# Hydro-Node.net
KiCad netlist of a schematic drawn in Altium Designer
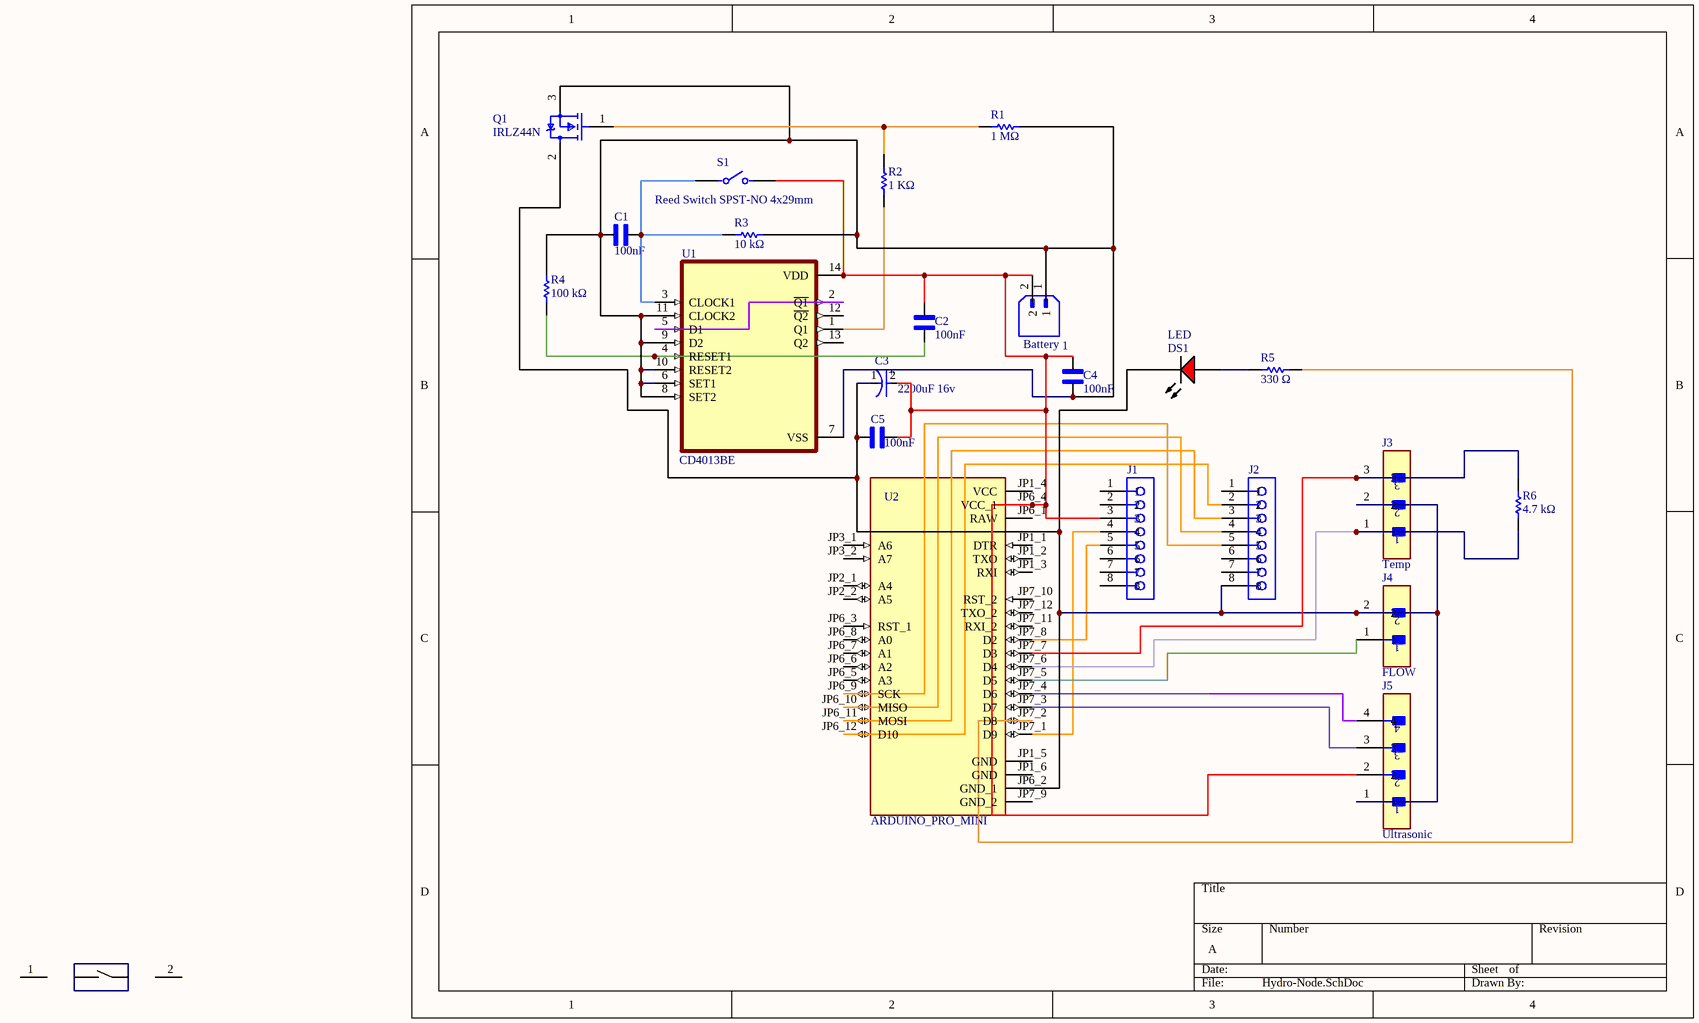
[diagram p0: Hydro-Node.SchDoc]

(export (version "E")
  (design (tool "Eeschema 10.0.6"))
  (components
    (comp (ref "1")
      (value "Battery")
      (footprint "JST_B2B-XH-A_(LF)(SN)")
      (description "Connector Header Through Hole 2 position 0.098 (2.50mm)")
      (fields (field (name "MF") "JST Sales") (field (name "MP") "B2B-XH-A (LF)(SN)"))
      (libsource (lib "B2B-XH-A__LF__SN_") (part "B2B-XH-A_(LF)(SN)"))
    )
    (comp (ref "C1")
      (value "100nF")
      (footprint "CAPRR508W50L508T317H508")
      (description "SR Series 5.08x5.08 mm 100 nF 50 V Â±20% Tol. Z5U Radial Lead/SkyCapÂ®")
      (fields (field (name "MF") "AVX") (field (name "MP") "SR215E104MARTR1"))
      (libsource (lib "") (part "SR215E104MARTR1._1"))
    )
    (comp (ref "C2")
      (value "100nF")
      (footprint "CAPRR508W50L508T317H508")
      (description "SR Series 5.08x5.08 mm 100 nF 50 V Â±20% Tol. Z5U Radial Lead/SkyCapÂ®")
      (fields (field (name "MF") "AVX") (field (name "MP") "SR215E104MARTR1"))
      (libsource (lib "SR215E104MARTR1.") (part "SR215E104MARTR1."))
    )
    (comp (ref "C3")
      (value "2200uF 16v")
      (footprint "FP-RAD-TH-D_10_0_5-L_16_1-MFG")
      (description "Aluminum Electrolytic Capacitors (Radial Lead Type) 2200uF ±20% 6.3V")
      (libsource (lib "Altium Content Vault") (part "a00bbbee19879c290e62620ae7e47b1"))
    )
    (comp (ref "C4")
      (value "100nF")
      (footprint "CAPRR508W50L508T317H508")
      (description "SR Series 5.08x5.08 mm 100 nF 50 V Â±20% Tol. Z5U Radial Lead/SkyCapÂ®")
      (fields (field (name "MF") "AVX") (field (name "MP") "SR215E104MARTR1"))
      (libsource (lib "SR215E104MARTR1.") (part "SR215E104MARTR1."))
    )
    (comp (ref "C5")
      (value "100nF")
      (footprint "CAPRR508W50L508T317H508")
      (description "SR Series 5.08x5.08 mm 100 nF 50 V Â±20% Tol. Z5U Radial Lead/SkyCapÂ®")
      (fields (field (name "MF") "AVX") (field (name "MP") "SR215E104MARTR1"))
      (libsource (lib "") (part "SR215E104MARTR1._1"))
    )
    (comp (ref "DS1")
      (value "LED")
      (footprint "INDPR60-254-520X380X650")
      (description "Radial LED, 12.6 mcd, 20 mA, 2 V, -55 to 100 degC, 2-Pin THD, RoHS, Bulk")
      (fields (field (name "TOLERANCE") "20%"))
      (libsource (lib "Altium Content Vault") (part "LED-RED-AK-2"))
    )
    (comp (ref "J1")
      (value "61300811821")
      (footprint "61300811821")
      (description "Btb Conn, Rcpt, 8Pos, 1Row, 2.54Mm Rohs Compliant: Yes")
      (libsource (lib "Altium Content Vault") (part "Header_Female_1R_08P"))
    )
    (comp (ref "J2")
      (value "61300811821")
      (footprint "61300811821")
      (description "Btb Conn, Rcpt, 8Pos, 1Row, 2.54Mm Rohs Compliant: Yes")
      (libsource (lib "Altium Content Vault") (part "Header_Female_1R_08P"))
    )
    (comp (ref "J3")
      (value "Temp")
      (footprint "FP-B3B-XH-A_LF_SN-MFG")
      (description "CONN HEADER VERT 3POS 2.5MM")
      (libsource (lib "Altium Content Vault") (part "0d3f023dd272f625e17a2be33dea85f"))
    )
    (comp (ref "J4")
      (value "FLOW")
      (footprint "FP-B2B-XH-AM_LF_SN-MFG")
      (description "CONN HEADER VERT 2POS 2.5MM")
      (libsource (lib "Altium Content Vault") (part "3bc925449376181038e59eaffc5286c"))
    )
    (comp (ref "J5")
      (value "Ultrasonic")
      (footprint "FP-B4B-XH-AM_LF_SN-MFG")
      (description "CONN HEADER VERT 4POS 2.5MM")
      (libsource (lib "Altium Content Vault") (part "299a8cea1bdcbc3624fe62c390fa72c"))
    )
    (comp (ref "Q1")
      (value "IRLZ44N")
      (footprint "FP-PG-TO220-3-MFG")
      (description "MOSFET N-CH 55V 47A TO220AB")
      (libsource (lib "Altium Content Vault") (part "b09f7f152735e370c1ea22a33fa83d6"))
    )
    (comp (ref "R1")
      (value "1 MΩ")
      (footprint "RESA60-630X240")
      (description "Axial Resistor, 1 MOhm, +/- 1%, 250 mW, -55 to 155 degC, 2-Pin THD, RoHS, Bulk")
      (fields (field (name "TOLERANCE") "1%"))
      (libsource (lib "Altium Content Vault") (part "RES-2"))
    )
    (comp (ref "R2")
      (value "1 KΩ")
      (footprint "RESA60-630X240")
      (description "Axial Resistor, 1 KOhm, +/- 1%, 250 mW, -55 to 155 degC, 2-Pin THD, RoHS, Bulk")
      (fields (field (name "TOLERANCE") "1%"))
      (libsource (lib "Altium Content Vault") (part "RES-2"))
    )
    (comp (ref "R3")
      (value "10 kΩ")
      (footprint "RESA60-630X240")
      (description "Axial Resistor, 10 KOhm, +/- 1%, 0.25 W, -55 to 155 degC, 2-Pin THD, RoHS, Bulk")
      (fields (field (name "TOLERANCE") "1%") (field (name "MANUFACTURER") "Yageo"))
      (libsource (lib "Altium Content Vault") (part "RES-2"))
    )
    (comp (ref "R4")
      (value "100 kΩ")
      (footprint "RESA60-630X240")
      (description "Axial Resistor, 100 KOhm, +/- 1%, 0.25 W, -55 to 155 degC, 2-Pin THD, RoHS, Bulk")
      (fields (field (name "TOLERANCE") "1%"))
      (libsource (lib "Altium Content Vault") (part "RES-2"))
    )
    (comp (ref "R5")
      (value "330 Ω")
      (footprint "RESA60-630X240")
      (description "Axial Resistor, 1 MOhm, +/- 1%, 250 mW, -55 to 155 degC, 2-Pin THD, RoHS, Bulk")
      (fields (field (name "TOLERANCE") "1%"))
      (libsource (lib "Altium Content Vault") (part "RES-2"))
    )
    (comp (ref "R6")
      (value "4.7 kΩ")
      (footprint "RESA60-630X240")
      (description "Axial Resistor, 4.75 KOhm, +/- 1%, 0.25 W, -55 to 155 degC, 2-Pin THD, RoHS, Bulk")
      (fields (field (name "TOLERANCE") "10%"))
      (libsource (lib "Altium Content Vault") (part "RES-2"))
    )
    (comp (ref "S1")
      (value "Reed Switch SPST-NO 4x29mm")
      (footprint "REEDSW-THT-D4L29-P35")
      (fields
        (field (name "MANUFACTURER PART NUMBER") "MDSM-4R-12-18")
        (field (name "OCTOPART") "https://octopart.com/mdsm-4r-12-18-littelfuse-55632078")
        (field (name "MANUFACTURER") "Littelfuse")
      )
      (libsource (lib "ReedSwitch") (part "REED-SWITCH-NO-D4L29"))
    )
    (comp (ref "U1")
      (value "CD4013BE")
      (footprint "DIP794W45P254L1969H508Q14")
      (description "CMOS Dual D-Type Flip Flop")
      (fields (field (name "MF") "Texas Instruments"))
      (libsource (lib "CD4013BE") (part "CD4013BE"))
    )
    (comp (ref "U2")
      (value "ARDUINO_PRO_MINI")
      (footprint "MODULE_ARDUINO_PRO_MINI")
      (fields (field (name "MF") "Arduino") (field (name "MP") "Arduino Pro Mini"))
      (libsource (lib "ARDUINO_PRO_MINI") (part "ARDUINO_PRO_MINI"))
    )
  )
  (nets
    (net (code "1") (name "Net-(C3-A)") (class "Default")
      (node (ref "1") (pin "2") (pinfunction "2_2") (pintype "passive"))
      (node (ref "C2") (pin "1") (pinfunction "1_1") (pintype "passive"))
      (node (ref "C3") (pin "2") (pinfunction "A_2") (pintype "passive"))
      (node (ref "C4") (pin "1") (pinfunction "1_1") (pintype "passive"))
      (node (ref "C5") (pin "2") (pinfunction "2_2") (pintype "passive"))
      (node (ref "J1") (pin "3") (pinfunction "3_3") (pintype "passive"))
      (node (ref "J5") (pin "2") (pinfunction "2_2") (pintype "passive"))
      (node (ref "S1") (pin "2") (pinfunction "2_2") (pintype "passive"))
      (node (ref "U1") (pin "14") (pinfunction "VDD_14") (pintype "power_in"))
      (node (ref "U2") (pin "JP6_4") (pinfunction "VCC_1_JP6_4") (pintype "power_in"))
    )
    (net (code "2") (name "Net-(C3-C)") (class "Default")
      (node (ref "C3") (pin "1") (pinfunction "C_1") (pintype "passive"))
      (node (ref "C5") (pin "1") (pinfunction "1_1") (pintype "passive"))
      (node (ref "DS1") (pin "2") (pinfunction "K_2") (pintype "passive"))
      (node (ref "J2") (pin "8") (pinfunction "8_8") (pintype "passive"))
      (node (ref "J3") (pin "2") (pinfunction "2_2") (pintype "passive"))
      (node (ref "J4") (pin "2") (pinfunction "2_2") (pintype "passive"))
      (node (ref "J5") (pin "1") (pinfunction "1_1") (pintype "passive"))
      (node (ref "Q1") (pin "2") (pinfunction "D_2") (pintype "passive"))
      (node (ref "U2") (pin "JP6_2") (pinfunction "GND_1_JP6_2") (pintype "power_in"))
    )
    (net (code "3") (name "Net-(DS1-A)") (class "Default")
      (node (ref "DS1") (pin "1") (pinfunction "A_1") (pintype "passive"))
      (node (ref "R5") (pin "1") (pinfunction "1_1") (pintype "passive"))
    )
    (net (code "4") (name "Net-(Q1-G)") (class "Default")
      (node (ref "Q1") (pin "1") (pinfunction "G_1") (pintype "passive"))
      (node (ref "R1") (pin "1") (pinfunction "1_1") (pintype "passive"))
      (node (ref "R2") (pin "2") (pinfunction "2_2") (pintype "passive"))
    )
    (net (code "5") (name "Net-(Q1-S)") (class "Default")
      (node (ref "1") (pin "1") (pinfunction "1_1") (pintype "passive"))
      (node (ref "C1") (pin "1") (pinfunction "1_1") (pintype "passive"))
      (node (ref "C4") (pin "2") (pinfunction "2_2") (pintype "passive"))
      (node (ref "Q1") (pin "3") (pinfunction "S_3") (pintype "passive"))
      (node (ref "R1") (pin "2") (pinfunction "2_2") (pintype "passive"))
      (node (ref "R3") (pin "2") (pinfunction "2_2") (pintype "passive"))
      (node (ref "R4") (pin "2") (pinfunction "2_2") (pintype "passive"))
      (node (ref "U1") (pin "10") (pinfunction "RESET2_10") (pintype "input"))
      (node (ref "U1") (pin "11") (pinfunction "CLOCK2_11") (pintype "input"))
      (node (ref "U1") (pin "6") (pinfunction "SET1_6") (pintype "input"))
      (node (ref "U1") (pin "7") (pinfunction "VSS_7") (pintype "power_in"))
      (node (ref "U1") (pin "8") (pinfunction "SET2_8") (pintype "input"))
      (node (ref "U1") (pin "9") (pinfunction "D2_9") (pintype "input"))
    )
    (net (code "6") (name "Net-(U1-CLOCK1)") (class "Default")
      (node (ref "C1") (pin "2") (pinfunction "2_2") (pintype "passive"))
      (node (ref "R3") (pin "1") (pinfunction "1_1") (pintype "passive"))
      (node (ref "S1") (pin "1") (pinfunction "1_1") (pintype "passive"))
      (node (ref "U1") (pin "3") (pinfunction "CLOCK1_3") (pintype "input"))
    )
    (net (code "7") (name "Net-(U1-D1)") (class "Default")
      (node (ref "U1") (pin "2") (pinfunction "~{Q1}_2") (pintype "output"))
      (node (ref "U1") (pin "5") (pinfunction "D1_5") (pintype "input"))
    )
    (net (code "8") (name "Net-(U1-Q1)") (class "Default")
      (node (ref "R2") (pin "1") (pinfunction "1_1") (pintype "passive"))
      (node (ref "U1") (pin "1") (pinfunction "Q1_1") (pintype "output"))
    )
    (net (code "9") (name "Net-(U1-RESET1)") (class "Default")
      (node (ref "C2") (pin "2") (pinfunction "2_2") (pintype "passive"))
      (node (ref "R4") (pin "1") (pinfunction "1_1") (pintype "passive"))
      (node (ref "U1") (pin "4") (pinfunction "RESET1_4") (pintype "input"))
    )
    (net (code "10") (name "Net-(U2-D2)") (class "Default")
      (node (ref "J1") (pin "5") (pinfunction "5_5") (pintype "passive"))
      (node (ref "U2") (pin "JP7_8") (pinfunction "D2_JP7_8") (pintype "bidirectional"))
    )
    (net (code "11") (name "Net-(U2-D3)") (class "Default")
      (node (ref "J3") (pin "3") (pinfunction "3_3") (pintype "passive"))
      (node (ref "R6") (pin "2") (pinfunction "2_2") (pintype "passive"))
      (node (ref "U2") (pin "JP7_7") (pinfunction "D3_JP7_7") (pintype "bidirectional"))
    )
    (net (code "12") (name "Net-(U2-D4)") (class "Default")
      (node (ref "J3") (pin "1") (pinfunction "1_1") (pintype "passive"))
      (node (ref "R6") (pin "1") (pinfunction "1_1") (pintype "passive"))
      (node (ref "U2") (pin "JP7_6") (pinfunction "D4_JP7_6") (pintype "bidirectional"))
    )
    (net (code "13") (name "Net-(U2-D5)") (class "Default")
      (node (ref "J4") (pin "1") (pinfunction "1_1") (pintype "passive"))
      (node (ref "U2") (pin "JP7_5") (pinfunction "D5_JP7_5") (pintype "bidirectional"))
    )
    (net (code "14") (name "Net-(U2-D6)") (class "Default")
      (node (ref "J5") (pin "4") (pinfunction "4_4") (pintype "passive"))
      (node (ref "U2") (pin "JP7_4") (pinfunction "D6_JP7_4") (pintype "bidirectional"))
    )
    (net (code "15") (name "Net-(U2-D7)") (class "Default")
      (node (ref "J5") (pin "3") (pinfunction "3_3") (pintype "passive"))
      (node (ref "U2") (pin "JP7_3") (pinfunction "D7_JP7_3") (pintype "bidirectional"))
    )
    (net (code "16") (name "Net-(U2-D8)") (class "Default")
      (node (ref "R5") (pin "2") (pinfunction "2_2") (pintype "passive"))
      (node (ref "U2") (pin "JP7_2") (pinfunction "D8_JP7_2") (pintype "bidirectional"))
    )
    (net (code "17") (name "Net-(U2-D9)") (class "Default")
      (node (ref "J1") (pin "4") (pinfunction "4_4") (pintype "passive"))
      (node (ref "U2") (pin "JP7_1") (pinfunction "D9_JP7_1") (pintype "bidirectional"))
    )
    (net (code "18") (name "Net-(U2-D10)") (class "Default")
      (node (ref "J2") (pin "2") (pinfunction "2_2") (pintype "passive"))
      (node (ref "U2") (pin "JP6_12") (pinfunction "D10_JP6_12") (pintype "bidirectional"))
    )
    (net (code "19") (name "Net-(U2-MISO)") (class "Default")
      (node (ref "J2") (pin "4") (pinfunction "4_4") (pintype "passive"))
      (node (ref "U2") (pin "JP6_10") (pinfunction "MISO_JP6_10") (pintype "bidirectional"))
    )
    (net (code "20") (name "Net-(U2-MOSI)") (class "Default")
      (node (ref "J2") (pin "3") (pinfunction "3_3") (pintype "passive"))
      (node (ref "U2") (pin "JP6_11") (pinfunction "MOSI_JP6_11") (pintype "bidirectional"))
    )
    (net (code "21") (name "Net-(U2-SCK)") (class "Default")
      (node (ref "J2") (pin "5") (pinfunction "5_5") (pintype "passive"))
      (node (ref "U2") (pin "JP6_9") (pinfunction "SCK_JP6_9") (pintype "bidirectional"))
    )
    (net (code "22") (name "unconnected-(J1-Pad1)") (class "Default")
      (node (ref "J1") (pin "1") (pinfunction "1_1") (pintype "passive"))
    )
    (net (code "23") (name "unconnected-(J1-Pad2)") (class "Default")
      (node (ref "J1") (pin "2") (pinfunction "2_2") (pintype "passive"))
    )
    (net (code "24") (name "unconnected-(J1-Pad6)") (class "Default")
      (node (ref "J1") (pin "6") (pinfunction "6_6") (pintype "passive"))
    )
    (net (code "25") (name "unconnected-(J1-Pad7)") (class "Default")
      (node (ref "J1") (pin "7") (pinfunction "7_7") (pintype "passive"))
    )
    (net (code "26") (name "unconnected-(J1-Pad8)") (class "Default")
      (node (ref "J1") (pin "8") (pinfunction "8_8") (pintype "passive"))
    )
    (net (code "27") (name "unconnected-(J2-Pad1)") (class "Default")
      (node (ref "J2") (pin "1") (pinfunction "1_1") (pintype "passive"))
    )
    (net (code "28") (name "unconnected-(J2-Pad6)") (class "Default")
      (node (ref "J2") (pin "6") (pinfunction "6_6") (pintype "passive"))
    )
    (net (code "29") (name "unconnected-(J2-Pad7)") (class "Default")
      (node (ref "J2") (pin "7") (pinfunction "7_7") (pintype "passive"))
    )
    (net (code "30") (name "unconnected-(S1-Pad1)") (class "Default")
      (node (ref "S1") (pin "1") (pinfunction "1_1") (pintype "passive"))
    )
    (net (code "31") (name "unconnected-(S1-Pad2)") (class "Default")
      (node (ref "S1") (pin "2") (pinfunction "2_2") (pintype "passive"))
    )
    (net (code "32") (name "unconnected-(U1-Q2-Pad13)") (class "Default")
      (node (ref "U1") (pin "13") (pinfunction "Q2_13") (pintype "output"))
    )
    (net (code "33") (name "unconnected-(U1-~{Q2}-Pad12)") (class "Default")
      (node (ref "U1") (pin "12") (pinfunction "~{Q2}_12") (pintype "output"))
    )
    (net (code "34") (name "unconnected-(U2-A0-PadJP6_8)") (class "Default")
      (node (ref "U2") (pin "JP6_8") (pinfunction "A0_JP6_8") (pintype "bidirectional"))
    )
    (net (code "35") (name "unconnected-(U2-A1-PadJP6_7)") (class "Default")
      (node (ref "U2") (pin "JP6_7") (pinfunction "A1_JP6_7") (pintype "bidirectional"))
    )
    (net (code "36") (name "unconnected-(U2-A2-PadJP6_6)") (class "Default")
      (node (ref "U2") (pin "JP6_6") (pinfunction "A2_JP6_6") (pintype "bidirectional"))
    )
    (net (code "37") (name "unconnected-(U2-A3-PadJP6_5)") (class "Default")
      (node (ref "U2") (pin "JP6_5") (pinfunction "A3_JP6_5") (pintype "bidirectional"))
    )
    (net (code "38") (name "unconnected-(U2-A4-PadJP2_1)") (class "Default")
      (node (ref "U2") (pin "JP2_1") (pinfunction "A4_JP2_1") (pintype "bidirectional"))
    )
    (net (code "39") (name "unconnected-(U2-A5-PadJP2_2)") (class "Default")
      (node (ref "U2") (pin "JP2_2") (pinfunction "A5_JP2_2") (pintype "bidirectional"))
    )
    (net (code "40") (name "unconnected-(U2-A6-PadJP3_1)") (class "Default")
      (node (ref "U2") (pin "JP3_1") (pinfunction "A6_JP3_1") (pintype "input"))
    )
    (net (code "41") (name "unconnected-(U2-A7-PadJP3_2)") (class "Default")
      (node (ref "U2") (pin "JP3_2") (pinfunction "A7_JP3_2") (pintype "input"))
    )
    (net (code "42") (name "unconnected-(U2-DTR-PadJP1_1)") (class "Default")
      (node (ref "U2") (pin "JP1_1") (pinfunction "DTR_JP1_1") (pintype "input"))
    )
    (net (code "43") (name "unconnected-(U2-GND-PadJP1_5)") (class "Default")
      (node (ref "U2") (pin "JP1_5") (pinfunction "GND_JP1_5") (pintype "power_in"))
    )
    (net (code "44") (name "unconnected-(U2-GND-PadJP1_6)") (class "Default")
      (node (ref "U2") (pin "JP1_6") (pinfunction "GND_JP1_6") (pintype "power_in"))
    )
    (net (code "45") (name "unconnected-(U2-GND_2-PadJP7_9)") (class "Default")
      (node (ref "U2") (pin "JP7_9") (pinfunction "GND_2_JP7_9") (pintype "power_in"))
    )
    (net (code "46") (name "unconnected-(U2-RAW-PadJP6_1)") (class "Default")
      (node (ref "U2") (pin "JP6_1") (pinfunction "RAW_JP6_1") (pintype "power_in"))
    )
    (net (code "47") (name "unconnected-(U2-RST_1-PadJP6_3)") (class "Default")
      (node (ref "U2") (pin "JP6_3") (pinfunction "RST_1_JP6_3") (pintype "input"))
    )
    (net (code "48") (name "unconnected-(U2-RST_2-PadJP7_10)") (class "Default")
      (node (ref "U2") (pin "JP7_10") (pinfunction "RST_2_JP7_10") (pintype "input"))
    )
    (net (code "49") (name "unconnected-(U2-RXI-PadJP1_3)") (class "Default")
      (node (ref "U2") (pin "JP1_3") (pinfunction "RXI_JP1_3") (pintype "bidirectional"))
    )
    (net (code "50") (name "unconnected-(U2-RXI_2-PadJP7_11)") (class "Default")
      (node (ref "U2") (pin "JP7_11") (pinfunction "RXI_2_JP7_11") (pintype "bidirectional"))
    )
    (net (code "51") (name "unconnected-(U2-TXO-PadJP1_2)") (class "Default")
      (node (ref "U2") (pin "JP1_2") (pinfunction "TXO_JP1_2") (pintype "bidirectional"))
    )
    (net (code "52") (name "unconnected-(U2-TXO_2-PadJP7_12)") (class "Default")
      (node (ref "U2") (pin "JP7_12") (pinfunction "TXO_2_JP7_12") (pintype "bidirectional"))
    )
    (net (code "53") (name "unconnected-(U2-VCC-PadJP1_4)") (class "Default")
      (node (ref "U2") (pin "JP1_4") (pinfunction "VCC_JP1_4") (pintype "power_in"))
    )
  )
)
